# LoginatorCore.net
KiCad netlist of a schematic drawn in EAGLE
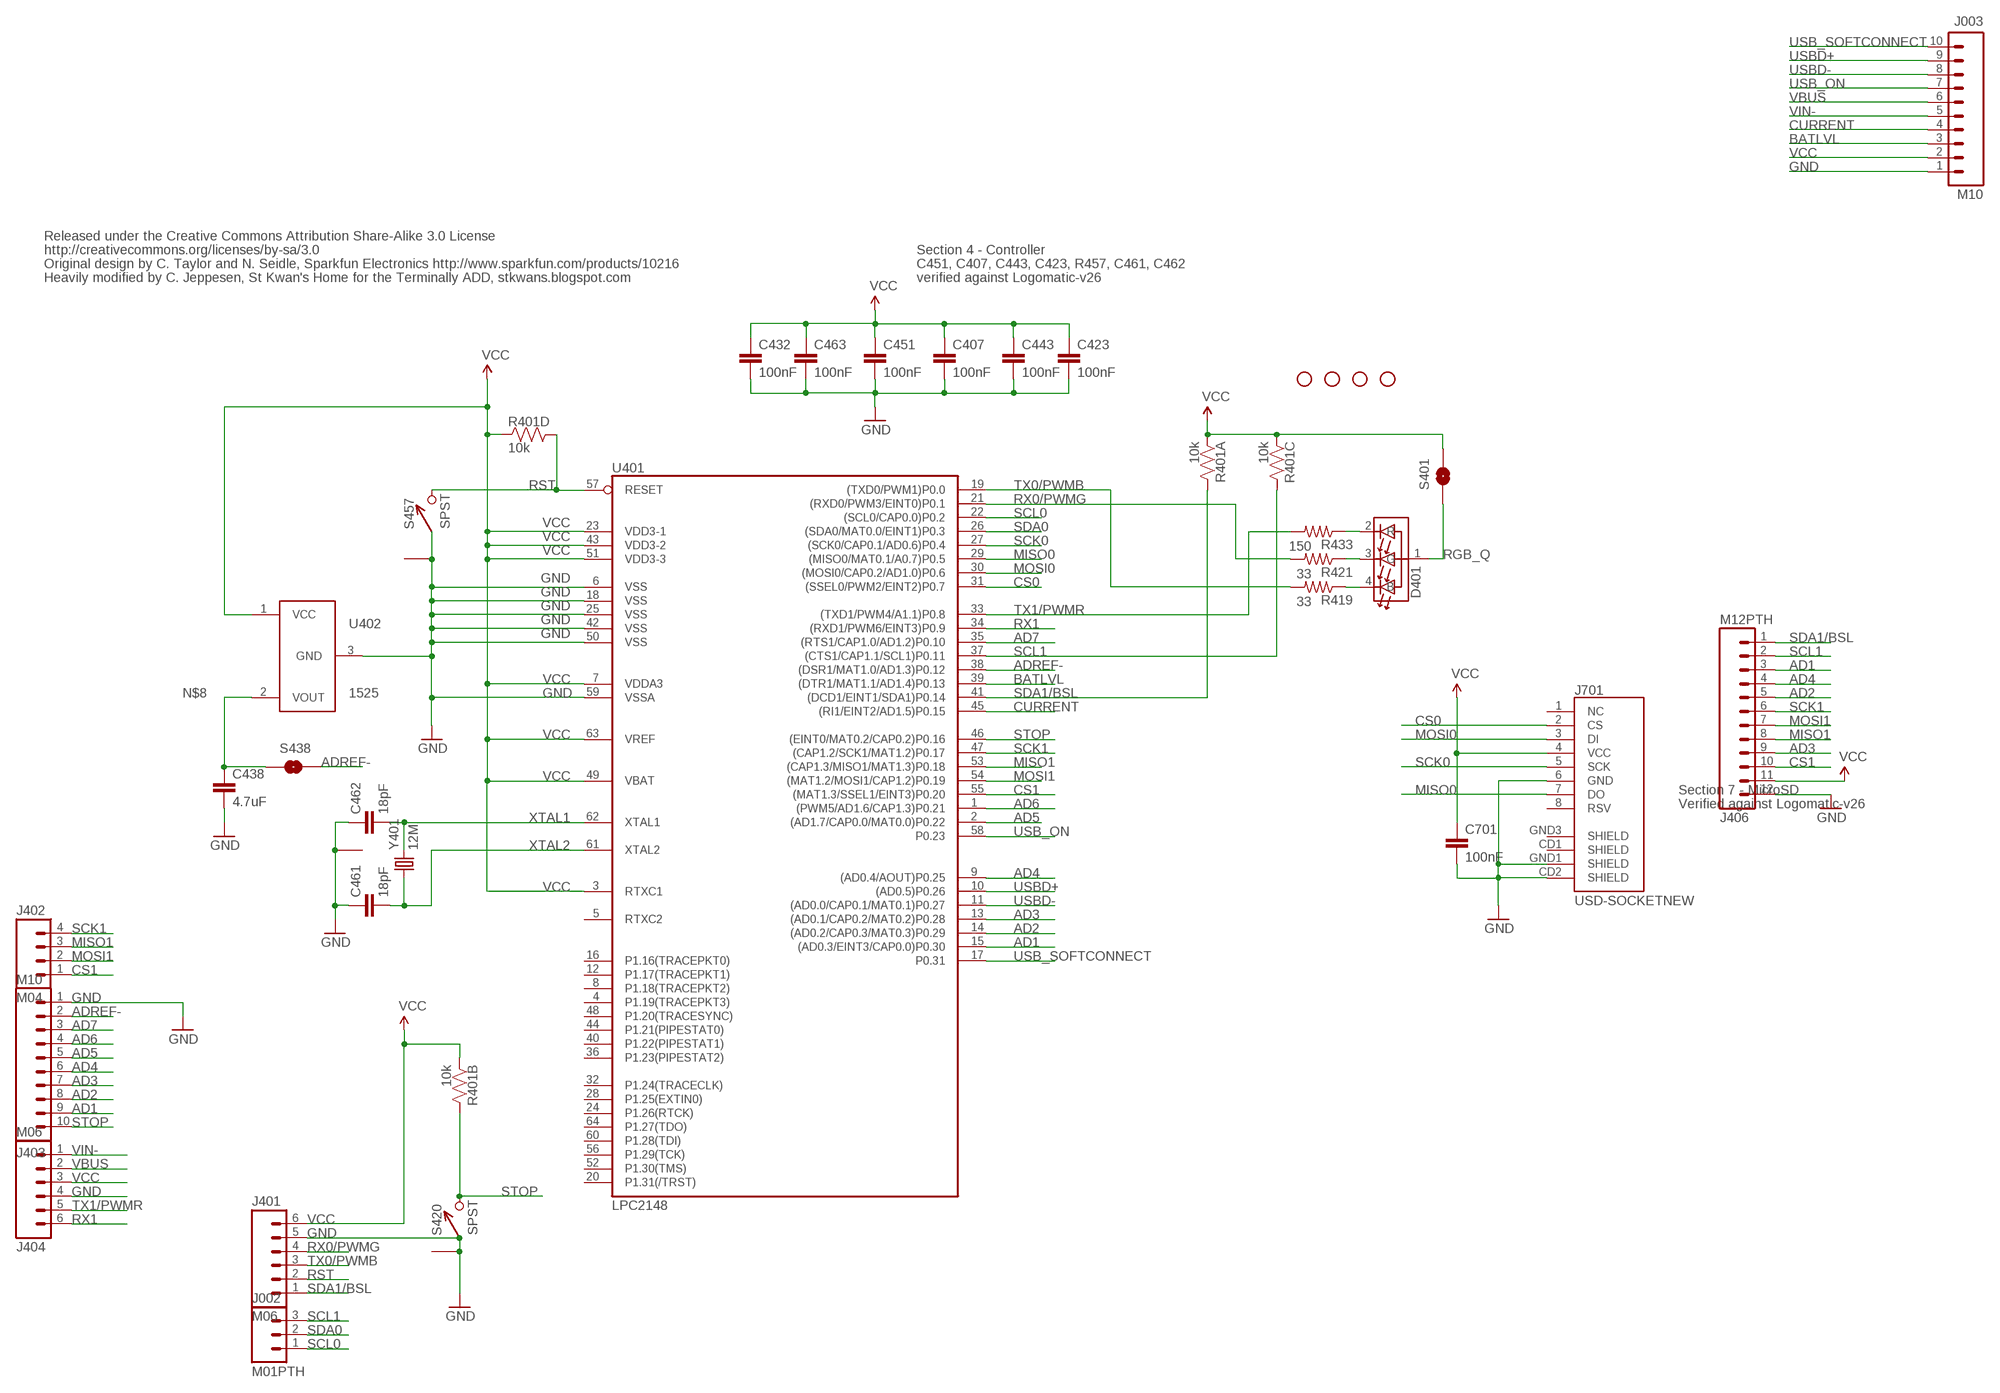
[diagram p0: schematic, sheet 1]

(export (version "E")
  (design (tool "Eeschema 10.0.6"))
  (components
    (comp (ref "C407")
      (value "100nF")
      (footprint "eagle-import:0402-CAP")
      (libsource (lib "eagle-import") (part "CAP0402-CAP"))
    )
    (comp (ref "C423")
      (value "100nF")
      (footprint "eagle-import:0402-CAP")
      (libsource (lib "eagle-import") (part "CAP0402-CAP"))
    )
    (comp (ref "C432")
      (value "100nF")
      (footprint "eagle-import:0402-CAP")
      (libsource (lib "eagle-import") (part "CAP0402-CAP"))
    )
    (comp (ref "C438")
      (value "4.7uF")
      (footprint "eagle-import:0402-CAP")
      (libsource (lib "eagle-import") (part "CAP0402-CAP"))
    )
    (comp (ref "C443")
      (value "100nF")
      (footprint "eagle-import:0402-CAP")
      (libsource (lib "eagle-import") (part "CAP0402-CAP"))
    )
    (comp (ref "C451")
      (value "100nF")
      (footprint "eagle-import:0402-CAP")
      (libsource (lib "eagle-import") (part "CAP0402-CAP"))
    )
    (comp (ref "C461")
      (value "18pF")
      (footprint "eagle-import:0402-CAP")
      (libsource (lib "eagle-import") (part "CAP0402-CAP"))
    )
    (comp (ref "C462")
      (value "18pF")
      (footprint "eagle-import:0402-CAP")
      (libsource (lib "eagle-import") (part "CAP0402-CAP"))
    )
    (comp (ref "C463")
      (value "100nF")
      (footprint "eagle-import:0402-CAP")
      (libsource (lib "eagle-import") (part "CAP0402-CAP"))
    )
    (comp (ref "C701")
      (value "100nF")
      (footprint "eagle-import:0402-CAP")
      (libsource (lib "eagle-import") (part "CAP0402-CAP"))
    )
    (comp (ref "D401")
      (value "HSMF-C118")
      (footprint "eagle-import:HSMF-C118")
      (libsource (lib "eagle-import") (part "HSMF-C118"))
    )
    (comp (ref "J002")
      (value "M01PTH")
      (footprint "eagle-import:1X03")
      (libsource (lib "eagle-import") (part "M03PTH"))
    )
    (comp (ref "J003")
      (value "M10")
      (footprint "eagle-import:1X10")
      (libsource (lib "eagle-import") (part "M10{dblquote}"))
    )
    (comp (ref "J401")
      (value "M06")
      (footprint "eagle-import:1X06")
      (libsource (lib "eagle-import") (part "M06SIP"))
    )
    (comp (ref "J402")
      (value "M04")
      (footprint "eagle-import:1X04")
      (libsource (lib "eagle-import") (part "M04PTH"))
    )
    (comp (ref "J403")
      (value "M10")
      (footprint "eagle-import:1X10")
      (libsource (lib "eagle-import") (part "M10{dblquote}"))
    )
    (comp (ref "J404")
      (value "M06")
      (footprint "eagle-import:1X06")
      (libsource (lib "eagle-import") (part "M06SIP"))
    )
    (comp (ref "J406")
      (value "M12PTH")
      (footprint "eagle-import:1X12")
      (libsource (lib "eagle-import") (part "M12PTH"))
    )
    (comp (ref "J701")
      (value "USD-SOCKETNEW")
      (footprint "eagle-import:MICRO-SD-SOCKET-PP")
      (libsource (lib "eagle-import") (part "USD-SOCKETNEW"))
    )
    (comp (ref "JP1")
      (value "STAND-OFF")
      (footprint "eagle-import:STAND-OFF")
      (libsource (lib "eagle-import") (part "STAND-OFF"))
    )
    (comp (ref "JP2")
      (value "STAND-OFF")
      (footprint "eagle-import:STAND-OFF")
      (libsource (lib "eagle-import") (part "STAND-OFF"))
    )
    (comp (ref "JP3")
      (value "STAND-OFF")
      (footprint "eagle-import:STAND-OFF")
      (libsource (lib "eagle-import") (part "STAND-OFF"))
    )
    (comp (ref "JP4")
      (value "STAND-OFF")
      (footprint "eagle-import:STAND-OFF")
      (libsource (lib "eagle-import") (part "STAND-OFF"))
    )
    (comp (ref "R401")
      (value "10k")
      (footprint "eagle-import:CRA04")
      (libsource (lib "eagle-import") (part "RP404"))
    )
    (comp (ref "R419")
      (value "33")
      (footprint "eagle-import:0402-RES")
      (libsource (lib "eagle-import") (part "RESISTOR0402-RES"))
    )
    (comp (ref "R421")
      (value "33")
      (footprint "eagle-import:0402-RES")
      (libsource (lib "eagle-import") (part "RESISTOR0402-RES"))
    )
    (comp (ref "R433")
      (value "150")
      (footprint "eagle-import:0402-RES")
      (libsource (lib "eagle-import") (part "RESISTOR0402-RES"))
    )
    (comp (ref "S401")
      (value "SOLDERJUMPERNO")
      (footprint "eagle-import:SJ_2S-NO")
      (libsource (lib "eagle-import") (part "SOLDERJUMPERNO"))
    )
    (comp (ref "S420")
      (value "SPST")
      (footprint "eagle-import:B3U-1100P")
      (libsource (lib "eagle-import") (part "B3U-1100P"))
    )
    (comp (ref "S438")
      (value "SOLDERJUMPERNO")
      (footprint "eagle-import:SJ_2S-NO")
      (libsource (lib "eagle-import") (part "SOLDERJUMPERNO"))
    )
    (comp (ref "S457")
      (value "SPST")
      (footprint "eagle-import:B3U-1100P")
      (libsource (lib "eagle-import") (part "B3U-1100P"))
    )
    (comp (ref "U401")
      (value "LPC2148")
      (footprint "eagle-import:SQFP-S-10X10-64")
      (libsource (lib "eagle-import") (part "LPC213X"))
    )
    (comp (ref "U402")
      (value "1525")
      (footprint "eagle-import:SOT-23-3")
      (libsource (lib "eagle-import") (part "MCP1525"))
    )
    (comp (ref "Y401")
      (value "12M")
      (footprint "eagle-import:CRYSTAL_SMD")
      (libsource (lib "eagle-import") (part "TSX-3225"))
    )
  )
  (nets
    (net (code "1") (name "/AD1") (class "Default")
      (node (ref "J403") (pin "9") (pinfunction "9_9") (pintype "passive"))
      (node (ref "J406") (pin "3") (pinfunction "3_3") (pintype "passive"))
      (node (ref "U401") (pin "15") (pinfunction "(AD0.3/EINT3/CAP0.0)P0.30_15") (pintype "bidirectional"))
    )
    (net (code "2") (name "/AD2") (class "Default")
      (node (ref "J403") (pin "8") (pinfunction "8_8") (pintype "passive"))
      (node (ref "J406") (pin "5") (pinfunction "5_5") (pintype "passive"))
      (node (ref "U401") (pin "14") (pinfunction "(AD0.2/CAP0.3/MAT0.3)P0.29_14") (pintype "bidirectional"))
    )
    (net (code "3") (name "/AD3") (class "Default")
      (node (ref "J403") (pin "7") (pinfunction "7_7") (pintype "passive"))
      (node (ref "J406") (pin "9") (pinfunction "9_9") (pintype "passive"))
      (node (ref "U401") (pin "13") (pinfunction "(AD0.1/CAP0.2/MAT0.2)P0.28_13") (pintype "bidirectional"))
    )
    (net (code "4") (name "/AD4") (class "Default")
      (node (ref "J403") (pin "6") (pinfunction "6_6") (pintype "passive"))
      (node (ref "J406") (pin "4") (pinfunction "4_4") (pintype "passive"))
      (node (ref "U401") (pin "9") (pinfunction "(AD0.4/AOUT)P0.25_9") (pintype "bidirectional"))
    )
    (net (code "5") (name "/AD5") (class "Default")
      (node (ref "J403") (pin "5") (pinfunction "5_5") (pintype "passive"))
      (node (ref "U401") (pin "2") (pinfunction "(AD1.7/CAP0.0/MAT0.0)P0.22_2") (pintype "bidirectional"))
    )
    (net (code "6") (name "/AD6") (class "Default")
      (node (ref "J403") (pin "4") (pinfunction "4_4") (pintype "passive"))
      (node (ref "U401") (pin "1") (pinfunction "(PWM5/AD1.6/CAP1.3)P0.21_1") (pintype "bidirectional"))
    )
    (net (code "7") (name "/AD7") (class "Default")
      (node (ref "J403") (pin "3") (pinfunction "3_3") (pintype "passive"))
      (node (ref "U401") (pin "35") (pinfunction "(RTS1/CAP1.0/AD1.2)P0.10_35") (pintype "bidirectional"))
    )
    (net (code "8") (name "/ADREF-") (class "Default")
      (node (ref "J403") (pin "2") (pinfunction "2_2") (pintype "passive"))
      (node (ref "S438") (pin "2") (pinfunction "2_2") (pintype "passive"))
      (node (ref "U401") (pin "38") (pinfunction "(DSR1/MAT1.0/AD1.3)P0.12_38") (pintype "bidirectional"))
    )
    (net (code "9") (name "/BATLVL") (class "Default")
      (node (ref "J003") (pin "3") (pinfunction "3_3") (pintype "passive"))
      (node (ref "U401") (pin "39") (pinfunction "(DTR1/MAT1.1/AD1.4)P0.13_39") (pintype "bidirectional"))
    )
    (net (code "10") (name "/CS0") (class "Default")
      (node (ref "J701") (pin "2") (pinfunction "CS_2") (pintype "bidirectional"))
      (node (ref "U401") (pin "31") (pinfunction "(SSEL0/PWM2/EINT2)P0.7_31") (pintype "bidirectional"))
    )
    (net (code "11") (name "/CS1") (class "Default")
      (node (ref "J402") (pin "1") (pinfunction "1_1") (pintype "passive"))
      (node (ref "J406") (pin "10") (pinfunction "10_10") (pintype "passive"))
      (node (ref "U401") (pin "55") (pinfunction "(MAT1.3/SSEL1/EINT3)P0.20_55") (pintype "bidirectional"))
    )
    (net (code "12") (name "/CURRENT") (class "Default")
      (node (ref "J003") (pin "4") (pinfunction "4_4") (pintype "passive"))
      (node (ref "U401") (pin "45") (pinfunction "(RI1/EINT2/AD1.5)P0.15_45") (pintype "bidirectional"))
    )
    (net (code "13") (name "/MISO0") (class "Default")
      (node (ref "J701") (pin "7") (pinfunction "DO_7") (pintype "bidirectional"))
      (node (ref "U401") (pin "29") (pinfunction "(MISO0/MAT0.1/A0.7)P0.5_29") (pintype "bidirectional"))
    )
    (net (code "14") (name "/MISO1") (class "Default")
      (node (ref "J402") (pin "3") (pinfunction "3_3") (pintype "passive"))
      (node (ref "J406") (pin "8") (pinfunction "8_8") (pintype "passive"))
      (node (ref "U401") (pin "53") (pinfunction "(CAP1.3/MISO1/MAT1.3)P0.18_53") (pintype "bidirectional"))
    )
    (net (code "15") (name "/MOSI0") (class "Default")
      (node (ref "J701") (pin "3") (pinfunction "DI_3") (pintype "bidirectional"))
      (node (ref "U401") (pin "30") (pinfunction "(MOSI0/CAP0.2/AD1.0)P0.6_30") (pintype "bidirectional"))
    )
    (net (code "16") (name "/MOSI1") (class "Default")
      (node (ref "J402") (pin "2") (pinfunction "2_2") (pintype "passive"))
      (node (ref "J406") (pin "7") (pinfunction "7_7") (pintype "passive"))
      (node (ref "U401") (pin "54") (pinfunction "(MAT1.2/MOSI1/CAP1.2)P0.19_54") (pintype "bidirectional"))
    )
    (net (code "17") (name "/N$8") (class "Default")
      (node (ref "C438") (pin "1") (pinfunction "1_1") (pintype "passive"))
      (node (ref "S438") (pin "1") (pinfunction "1_1") (pintype "passive"))
      (node (ref "U402") (pin "2") (pinfunction "VOUT_2") (pintype "bidirectional"))
    )
    (net (code "18") (name "/RGB_Q") (class "Default")
      (node (ref "D401") (pin "1") (pinfunction "A_1") (pintype "passive"))
      (node (ref "S401") (pin "1") (pinfunction "1_1") (pintype "passive"))
    )
    (net (code "19") (name "/RST") (class "Default")
      (node (ref "J401") (pin "2") (pinfunction "2_2") (pintype "passive"))
      (node (ref "R401") (pin "5") (pinfunction "2_5") (pintype "passive"))
      (node (ref "S457") (pin "P$2") (pinfunction "2_P$2") (pintype "bidirectional"))
      (node (ref "U401") (pin "57") (pinfunction "RESET_57") (pintype "input"))
    )
    (net (code "20") (name "/RX0{slash}PWMG") (class "Default")
      (node (ref "J401") (pin "4") (pinfunction "4_4") (pintype "passive"))
      (node (ref "R421") (pin "2") (pinfunction "2_2") (pintype "passive"))
      (node (ref "U401") (pin "21") (pinfunction "(RXD0/PWM3/EINT0)P0.1_21") (pintype "bidirectional"))
    )
    (net (code "21") (name "/RX1") (class "Default")
      (node (ref "J404") (pin "6") (pinfunction "6_6") (pintype "passive"))
      (node (ref "U401") (pin "34") (pinfunction "(RXD1/PWM6/EINT3)P0.9_34") (pintype "bidirectional"))
    )
    (net (code "22") (name "/SCK0") (class "Default")
      (node (ref "J701") (pin "5") (pinfunction "SCK_5") (pintype "bidirectional"))
      (node (ref "U401") (pin "27") (pinfunction "(SCK0/CAP0.1/AD0.6)P0.4_27") (pintype "bidirectional"))
    )
    (net (code "23") (name "/SCK1") (class "Default")
      (node (ref "J402") (pin "4") (pinfunction "4_4") (pintype "passive"))
      (node (ref "J406") (pin "6") (pinfunction "6_6") (pintype "passive"))
      (node (ref "U401") (pin "47") (pinfunction "(CAP1.2/SCK1/MAT1.2)P0.17_47") (pintype "bidirectional"))
    )
    (net (code "24") (name "/SCL0") (class "Default")
      (node (ref "J002") (pin "1") (pinfunction "1_1") (pintype "passive"))
      (node (ref "U401") (pin "22") (pinfunction "(SCL0/CAP0.0)P0.2_22") (pintype "bidirectional"))
    )
    (net (code "25") (name "/SCL1") (class "Default")
      (node (ref "J002") (pin "3") (pinfunction "3_3") (pintype "passive"))
      (node (ref "J406") (pin "2") (pinfunction "2_2") (pintype "passive"))
      (node (ref "R401") (pin "6") (pinfunction "2_6") (pintype "passive"))
      (node (ref "U401") (pin "37") (pinfunction "(CTS1/CAP1.1/SCL1)P0.11_37") (pintype "bidirectional"))
    )
    (net (code "26") (name "/SDA0") (class "Default")
      (node (ref "J002") (pin "2") (pinfunction "2_2") (pintype "passive"))
      (node (ref "U401") (pin "26") (pinfunction "(SDA0/MAT0.0/EINT1)P0.3_26") (pintype "bidirectional"))
    )
    (net (code "27") (name "/SDA1{slash}BSL") (class "Default")
      (node (ref "J401") (pin "1") (pinfunction "1_1") (pintype "passive"))
      (node (ref "J406") (pin "1") (pinfunction "1_1") (pintype "passive"))
      (node (ref "R401") (pin "8") (pinfunction "2_8") (pintype "passive"))
      (node (ref "U401") (pin "41") (pinfunction "(DCD1/EINT1/SDA1)P0.14_41") (pintype "bidirectional"))
    )
    (net (code "28") (name "/STOP") (class "Default")
      (node (ref "J403") (pin "10") (pinfunction "10_10") (pintype "passive"))
      (node (ref "R401") (pin "7") (pinfunction "2_7") (pintype "passive"))
      (node (ref "S420") (pin "P$2") (pinfunction "2_P$2") (pintype "bidirectional"))
      (node (ref "U401") (pin "46") (pinfunction "(EINT0/MAT0.2/CAP0.2)P0.16_46") (pintype "bidirectional"))
    )
    (net (code "29") (name "/TX0{slash}PWMB") (class "Default")
      (node (ref "J401") (pin "3") (pinfunction "3_3") (pintype "passive"))
      (node (ref "R419") (pin "2") (pinfunction "2_2") (pintype "passive"))
      (node (ref "U401") (pin "19") (pinfunction "(TXD0/PWM1)P0.0_19") (pintype "bidirectional"))
    )
    (net (code "30") (name "/TX1{slash}PWMR") (class "Default")
      (node (ref "J404") (pin "5") (pinfunction "5_5") (pintype "passive"))
      (node (ref "R433") (pin "2") (pinfunction "2_2") (pintype "passive"))
      (node (ref "U401") (pin "33") (pinfunction "(TXD1/PWM4/A1.1)P0.8_33") (pintype "bidirectional"))
    )
    (net (code "31") (name "/USBD+") (class "Default")
      (node (ref "J003") (pin "9") (pinfunction "9_9") (pintype "passive"))
      (node (ref "U401") (pin "10") (pinfunction "(AD0.5)P0.26_10") (pintype "bidirectional"))
    )
    (net (code "32") (name "/USBD-") (class "Default")
      (node (ref "J003") (pin "8") (pinfunction "8_8") (pintype "passive"))
      (node (ref "U401") (pin "11") (pinfunction "(AD0.0/CAP0.1/MAT0.1)P0.27_11") (pintype "bidirectional"))
    )
    (net (code "33") (name "/USB_ON") (class "Default")
      (node (ref "J003") (pin "7") (pinfunction "7_7") (pintype "passive"))
      (node (ref "U401") (pin "58") (pinfunction "P0.23_58") (pintype "bidirectional"))
    )
    (net (code "34") (name "/USB_SOFTCONNECT") (class "Default")
      (node (ref "J003") (pin "10") (pinfunction "10_10") (pintype "passive"))
      (node (ref "U401") (pin "17") (pinfunction "P0.31_17") (pintype "output"))
    )
    (net (code "35") (name "/VBUS") (class "Default")
      (node (ref "J003") (pin "6") (pinfunction "6_6") (pintype "passive"))
      (node (ref "J404") (pin "2") (pinfunction "2_2") (pintype "passive"))
    )
    (net (code "36") (name "/VIN-") (class "Default")
      (node (ref "J003") (pin "5") (pinfunction "5_5") (pintype "passive"))
      (node (ref "J404") (pin "1") (pinfunction "1_1") (pintype "passive"))
    )
    (net (code "37") (name "/XTAL1") (class "Default")
      (node (ref "C462") (pin "2") (pinfunction "2_2") (pintype "passive"))
      (node (ref "U401") (pin "62") (pinfunction "XTAL1_62") (pintype "input"))
      (node (ref "Y401") (pin "3") (pinfunction "2_3") (pintype "passive"))
    )
    (net (code "38") (name "/XTAL2") (class "Default")
      (node (ref "C461") (pin "2") (pinfunction "2_2") (pintype "passive"))
      (node (ref "U401") (pin "61") (pinfunction "XTAL2_61") (pintype "output"))
      (node (ref "Y401") (pin "1") (pinfunction "1_1") (pintype "passive"))
    )
    (net (code "39") (name "GND") (class "Default")
      (node (ref "C407") (pin "2") (pinfunction "2_2") (pintype "passive"))
      (node (ref "C423") (pin "2") (pinfunction "2_2") (pintype "passive"))
      (node (ref "C432") (pin "2") (pinfunction "2_2") (pintype "passive"))
      (node (ref "C438") (pin "2") (pinfunction "2_2") (pintype "passive"))
      (node (ref "C443") (pin "2") (pinfunction "2_2") (pintype "passive"))
      (node (ref "C451") (pin "2") (pinfunction "2_2") (pintype "passive"))
      (node (ref "C461") (pin "1") (pinfunction "1_1") (pintype "passive"))
      (node (ref "C462") (pin "1") (pinfunction "1_1") (pintype "passive"))
      (node (ref "C463") (pin "2") (pinfunction "2_2") (pintype "passive"))
      (node (ref "C701") (pin "2") (pinfunction "2_2") (pintype "passive"))
      (node (ref "J003") (pin "1") (pinfunction "1_1") (pintype "passive"))
      (node (ref "J401") (pin "5") (pinfunction "5_5") (pintype "passive"))
      (node (ref "J403") (pin "1") (pinfunction "1_1") (pintype "passive"))
      (node (ref "J404") (pin "4") (pinfunction "4_4") (pintype "passive"))
      (node (ref "J406") (pin "12") (pinfunction "12_12") (pintype "passive"))
      (node (ref "J701") (pin "6") (pinfunction "GND_6") (pintype "bidirectional"))
      (node (ref "J701") (pin "CD2") (pinfunction "SHIELD_CD2") (pintype "bidirectional"))
      (node (ref "J701") (pin "GND1") (pinfunction "SHIELD_GND1") (pintype "bidirectional"))
      (node (ref "S420") (pin "P$1") (pinfunction "1_P$1") (pintype "bidirectional"))
      (node (ref "S420") (pin "P$3") (pinfunction "1_P$3") (pintype "bidirectional"))
      (node (ref "S457") (pin "P$1") (pinfunction "1_P$1") (pintype "bidirectional"))
      (node (ref "S457") (pin "P$3") (pinfunction "1_P$3") (pintype "bidirectional"))
      (node (ref "U401") (pin "18") (pinfunction "VSS_18") (pintype "power_in"))
      (node (ref "U401") (pin "25") (pinfunction "VSS_25") (pintype "power_in"))
      (node (ref "U401") (pin "42") (pinfunction "VSS_42") (pintype "power_in"))
      (node (ref "U401") (pin "50") (pinfunction "VSS_50") (pintype "power_in"))
      (node (ref "U401") (pin "59") (pinfunction "VSSA_59") (pintype "power_in"))
      (node (ref "U401") (pin "6") (pinfunction "VSS_6") (pintype "power_in"))
      (node (ref "U402") (pin "3") (pinfunction "GND_3") (pintype "bidirectional"))
      (node (ref "Y401") (pin "2") (pinfunction "1_2") (pintype "bidirectional"))
      (node (ref "Y401") (pin "4") (pinfunction "1_4") (pintype "bidirectional"))
    )
    (net (code "40") (name "Net-(D401-B)") (class "Default")
      (node (ref "D401") (pin "4") (pinfunction "B_4") (pintype "passive"))
      (node (ref "R419") (pin "1") (pinfunction "1_1") (pintype "passive"))
    )
    (net (code "41") (name "Net-(D401-G)") (class "Default")
      (node (ref "D401") (pin "3") (pinfunction "G_3") (pintype "passive"))
      (node (ref "R421") (pin "1") (pinfunction "1_1") (pintype "passive"))
    )
    (net (code "42") (name "Net-(D401-R)") (class "Default")
      (node (ref "D401") (pin "2") (pinfunction "R_2") (pintype "passive"))
      (node (ref "R433") (pin "1") (pinfunction "1_1") (pintype "passive"))
    )
    (net (code "43") (name "VCC") (class "Default")
      (node (ref "C407") (pin "1") (pinfunction "1_1") (pintype "passive"))
      (node (ref "C423") (pin "1") (pinfunction "1_1") (pintype "passive"))
      (node (ref "C432") (pin "1") (pinfunction "1_1") (pintype "passive"))
      (node (ref "C443") (pin "1") (pinfunction "1_1") (pintype "passive"))
      (node (ref "C451") (pin "1") (pinfunction "1_1") (pintype "passive"))
      (node (ref "C463") (pin "1") (pinfunction "1_1") (pintype "passive"))
      (node (ref "C701") (pin "1") (pinfunction "1_1") (pintype "passive"))
      (node (ref "J003") (pin "2") (pinfunction "2_2") (pintype "passive"))
      (node (ref "J401") (pin "6") (pinfunction "6_6") (pintype "passive"))
      (node (ref "J404") (pin "3") (pinfunction "3_3") (pintype "passive"))
      (node (ref "J406") (pin "11") (pinfunction "11_11") (pintype "passive"))
      (node (ref "J701") (pin "4") (pinfunction "VCC_4") (pintype "bidirectional"))
      (node (ref "R401") (pin "1") (pinfunction "1_1") (pintype "passive"))
      (node (ref "R401") (pin "2") (pinfunction "1_2") (pintype "passive"))
      (node (ref "R401") (pin "3") (pinfunction "1_3") (pintype "passive"))
      (node (ref "R401") (pin "4") (pinfunction "1_4") (pintype "passive"))
      (node (ref "S401") (pin "2") (pinfunction "2_2") (pintype "passive"))
      (node (ref "U401") (pin "23") (pinfunction "VDD3-1_23") (pintype "power_in"))
      (node (ref "U401") (pin "3") (pinfunction "RTXC1_3") (pintype "input"))
      (node (ref "U401") (pin "43") (pinfunction "VDD3-2_43") (pintype "power_in"))
      (node (ref "U401") (pin "49") (pinfunction "VBAT_49") (pintype "power_in"))
      (node (ref "U401") (pin "51") (pinfunction "VDD3-3_51") (pintype "power_in"))
      (node (ref "U401") (pin "63") (pinfunction "VREF_63") (pintype "input"))
      (node (ref "U401") (pin "7") (pinfunction "VDDA3_7") (pintype "power_in"))
      (node (ref "U402") (pin "1") (pinfunction "VCC_1") (pintype "bidirectional"))
    )
    (net (code "44") (name "unconnected-(J701-NC-Pad1)") (class "Default")
      (node (ref "J701") (pin "1") (pinfunction "NC_1") (pintype "bidirectional"))
    )
    (net (code "45") (name "unconnected-(J701-RSV-Pad8)") (class "Default")
      (node (ref "J701") (pin "8") (pinfunction "RSV_8") (pintype "bidirectional"))
    )
    (net (code "46") (name "unconnected-(J701-SHIELD-PadCD1)") (class "Default")
      (node (ref "J701") (pin "CD1") (pinfunction "SHIELD_CD1") (pintype "bidirectional"))
    )
    (net (code "47") (name "unconnected-(J701-SHIELD-PadGND3)") (class "Default")
      (node (ref "J701") (pin "GND3") (pinfunction "SHIELD_GND3") (pintype "bidirectional"))
    )
    (net (code "48") (name "unconnected-(U401-P1.16(TRACEPKT0)-Pad16)") (class "Default")
      (node (ref "U401") (pin "16") (pinfunction "P1.16(TRACEPKT0)_16") (pintype "bidirectional"))
    )
    (net (code "49") (name "unconnected-(U401-P1.17(TRACEPKT1)-Pad12)") (class "Default")
      (node (ref "U401") (pin "12") (pinfunction "P1.17(TRACEPKT1)_12") (pintype "bidirectional"))
    )
    (net (code "50") (name "unconnected-(U401-P1.18(TRACEPKT2)-Pad8)") (class "Default")
      (node (ref "U401") (pin "8") (pinfunction "P1.18(TRACEPKT2)_8") (pintype "bidirectional"))
    )
    (net (code "51") (name "unconnected-(U401-P1.19(TRACEPKT3)-Pad4)") (class "Default")
      (node (ref "U401") (pin "4") (pinfunction "P1.19(TRACEPKT3)_4") (pintype "bidirectional"))
    )
    (net (code "52") (name "unconnected-(U401-P1.20(TRACESYNC)-Pad48)") (class "Default")
      (node (ref "U401") (pin "48") (pinfunction "P1.20(TRACESYNC)_48") (pintype "bidirectional"))
    )
    (net (code "53") (name "unconnected-(U401-P1.21(PIPESTAT0)-Pad44)") (class "Default")
      (node (ref "U401") (pin "44") (pinfunction "P1.21(PIPESTAT0)_44") (pintype "bidirectional"))
    )
    (net (code "54") (name "unconnected-(U401-P1.22(PIPESTAT1)-Pad40)") (class "Default")
      (node (ref "U401") (pin "40") (pinfunction "P1.22(PIPESTAT1)_40") (pintype "bidirectional"))
    )
    (net (code "55") (name "unconnected-(U401-P1.23(PIPESTAT2)-Pad36)") (class "Default")
      (node (ref "U401") (pin "36") (pinfunction "P1.23(PIPESTAT2)_36") (pintype "bidirectional"))
    )
    (net (code "56") (name "unconnected-(U401-P1.24(TRACECLK)-Pad32)") (class "Default")
      (node (ref "U401") (pin "32") (pinfunction "P1.24(TRACECLK)_32") (pintype "bidirectional"))
    )
    (net (code "57") (name "unconnected-(U401-P1.25(EXTIN0)-Pad28)") (class "Default")
      (node (ref "U401") (pin "28") (pinfunction "P1.25(EXTIN0)_28") (pintype "bidirectional"))
    )
    (net (code "58") (name "unconnected-(U401-P1.26(RTCK)-Pad24)") (class "Default")
      (node (ref "U401") (pin "24") (pinfunction "P1.26(RTCK)_24") (pintype "bidirectional"))
    )
    (net (code "59") (name "unconnected-(U401-P1.27(TDO)-Pad64)") (class "Default")
      (node (ref "U401") (pin "64") (pinfunction "P1.27(TDO)_64") (pintype "bidirectional"))
    )
    (net (code "60") (name "unconnected-(U401-P1.28(TDI)-Pad60)") (class "Default")
      (node (ref "U401") (pin "60") (pinfunction "P1.28(TDI)_60") (pintype "bidirectional"))
    )
    (net (code "61") (name "unconnected-(U401-P1.29(TCK)-Pad56)") (class "Default")
      (node (ref "U401") (pin "56") (pinfunction "P1.29(TCK)_56") (pintype "bidirectional"))
    )
    (net (code "62") (name "unconnected-(U401-P1.30(TMS)-Pad52)") (class "Default")
      (node (ref "U401") (pin "52") (pinfunction "P1.30(TMS)_52") (pintype "bidirectional"))
    )
    (net (code "63") (name "unconnected-(U401-P1.31({slash}TRST)-Pad20)") (class "Default")
      (node (ref "U401") (pin "20") (pinfunction "P1.31(/TRST)_20") (pintype "bidirectional"))
    )
    (net (code "64") (name "unconnected-(U401-RTXC2-Pad5)") (class "Default")
      (node (ref "U401") (pin "5") (pinfunction "RTXC2_5") (pintype "output"))
    )
  )
)
